# vswr.net
KiCad netlist of a schematic drawn in Altium Designer
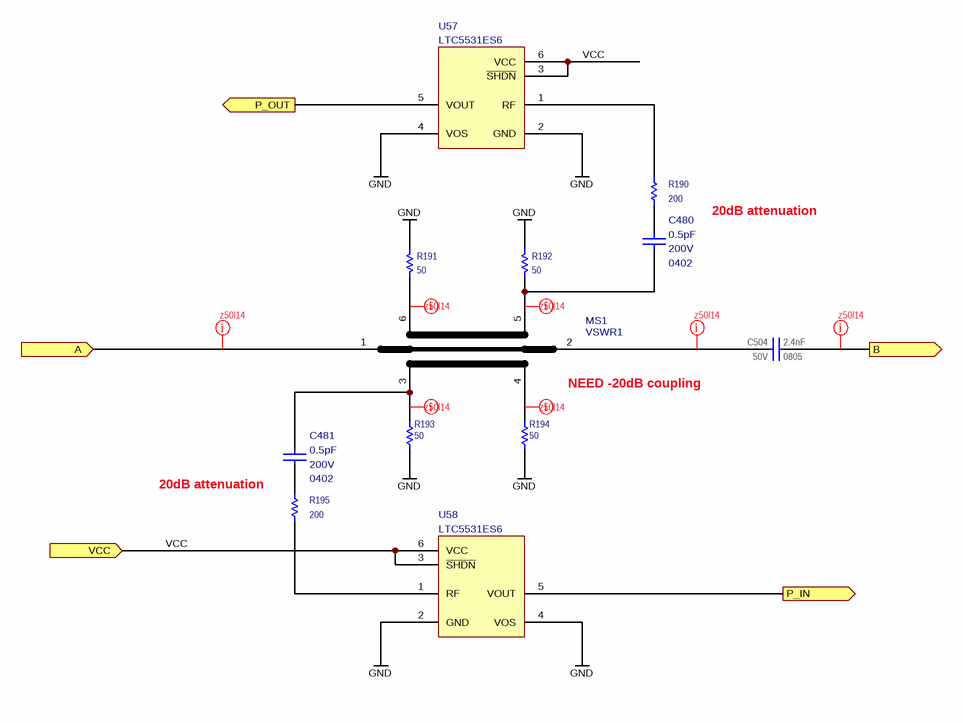
[diagram p0: vswr.SchDoc]

(export (version "E")
  (design (tool "Eeschema 10.0.6"))
  (components
    (comp (ref "C480")
      (value "0.5pF")
      (footprint "CAPC100X50X55L25N")
      (description "Ceramic Capacitor 0.5pF ±0.05pF 200V C0G 0402")
      (fields
        (field (name "MANUFACTURER") "American Technical Ceramics")
        (field (name "TOLERANCE") "±0.05pF")
        (field (name "PACKAGE") "0402")
        (field (name "VOLTAGE") "200V")
      )
      (libsource (lib "capacitors") (part "CAP"))
    )
    (comp (ref "C481")
      (value "0.5pF")
      (footprint "CAPC100X50X55L25N")
      (description "Ceramic Capacitor 0.5pF ±0.05pF 200V C0G 0402")
      (fields
        (field (name "MANUFACTURER") "American Technical Ceramics")
        (field (name "TOLERANCE") "±0.05pF")
        (field (name "PACKAGE") "0402")
        (field (name "VOLTAGE") "200V")
      )
      (libsource (lib "capacitors") (part "CAP"))
    )
    (comp (ref "C504")
      (value "2.4nF")
      (footprint "CAPC2012X145N")
      (description "Ceramic Capacitor 2.4nF 50V 0805")
      (fields
        (field (name "MANUFACTURER") "Dielectric Laboratories")
        (field (name "VOLTAGE") "50V")
        (field (name "PACKAGE") "0805")
        (field (name "Comment") "C08BL242X-5UN-X0T")
      )
      (libsource (lib "generic") (part "CAP"))
    )
    (comp (ref "MS1")
      (value "VSWR1")
      (footprint "graviton:VSWR1")
      (description "VSWR Meter Stripline")
      (libsource (lib "Graviton") (part "VSWR1"))
    )
    (comp (ref "R190")
      (value "200")
      (footprint "generic:RESC1005X40N")
      (description "Thin Film RF Resistor 200 Ohm ±0.1% 0402")
      (fields (field (name "MANUFACTURER") "Vishay") (field (name "TOLERANCE") "±0.1%"))
      (libsource (lib "Graviton") (part "RES 0603"))
    )
    (comp (ref "R191")
      (value "50")
      (footprint "generic:RESC1005X40N")
      (description "Thin Film RF Resistor 50 Ohm ±0.1% 0402")
      (fields (field (name "MANUFACTURER") "Vishay") (field (name "TOLERANCE") "±0.1%"))
      (libsource (lib "Graviton") (part "RES 0603"))
    )
    (comp (ref "R192")
      (value "50")
      (footprint "generic:RESC1005X40N")
      (description "Thin Film RF Resistor 50 Ohm ±0.1% 0402")
      (fields (field (name "MANUFACTURER") "Vishay") (field (name "TOLERANCE") "±0.1%"))
      (libsource (lib "Graviton") (part "RES 0603"))
    )
    (comp (ref "R193")
      (value "50")
      (footprint "generic:RESC1005X40N")
      (description "Thin Film RF Resistor 50 Ohm ±0.1% 0402")
      (fields (field (name "MANUFACTURER") "Vishay") (field (name "TOLERANCE") "±0.1%"))
      (libsource (lib "Graviton") (part "RES 0603"))
    )
    (comp (ref "R194")
      (value "50")
      (footprint "generic:RESC1005X40N")
      (description "Thin Film RF Resistor 50 Ohm ±0.1% 0402")
      (fields (field (name "MANUFACTURER") "Vishay") (field (name "TOLERANCE") "±0.1%"))
      (libsource (lib "Graviton") (part "RES 0603"))
    )
    (comp (ref "R195")
      (value "200")
      (footprint "generic:RESC1005X40N")
      (description "Thin Film RF Resistor 200 Ohm ±0.1% 0402")
      (fields (field (name "MANUFACTURER") "Vishay") (field (name "TOLERANCE") "±0.1%"))
      (libsource (lib "Graviton") (part "RES 0603"))
    )
    (comp (ref "U57")
      (value "LTC5531ES6")
      (footprint "generic:SOT23-6")
      (description "RF Detector")
      (fields (field (name "MANUFACTURER") "Linear Technology"))
      (libsource (lib "") (part "LTC5531ES6_1"))
    )
    (comp (ref "U58")
      (value "LTC5531ES6")
      (footprint "generic:SOT23-6")
      (description "RF Detector")
      (fields (field (name "MANUFACTURER") "Linear Technology"))
      (libsource (lib "linear") (part "LTC5531ES6"))
    )
  )
  (nets
    (net (code "1") (name "/A") (class "Default")
      (node (ref "MS1") (pin "1") (pinfunction "S1_1") (pintype "passive"))
    )
    (net (code "2") (name "/B") (class "Default")
      (node (ref "C504") (pin "1") (pinfunction "1_1") (pintype "passive"))
    )
    (net (code "3") (name "/P_IN") (class "Default")
      (node (ref "U58") (pin "5") (pinfunction "VOUT_5") (pintype "passive"))
    )
    (net (code "4") (name "/P_OUT") (class "Default")
      (node (ref "U57") (pin "5") (pinfunction "VOUT_5") (pintype "passive"))
    )
    (net (code "5") (name "/VCC") (class "Default")
      (node (ref "U57") (pin "3") (pinfunction "SHDN_3") (pintype "passive"))
      (node (ref "U57") (pin "6") (pinfunction "VCC_6") (pintype "passive"))
      (node (ref "U58") (pin "3") (pinfunction "SHDN_3") (pintype "passive"))
      (node (ref "U58") (pin "6") (pinfunction "VCC_6") (pintype "passive"))
    )
    (net (code "6") (name "GND") (class "Default")
      (node (ref "R191") (pin "1") (pinfunction "1_1") (pintype "passive"))
      (node (ref "R192") (pin "1") (pinfunction "1_1") (pintype "passive"))
      (node (ref "R193") (pin "1") (pinfunction "1_1") (pintype "passive"))
      (node (ref "R194") (pin "1") (pinfunction "1_1") (pintype "passive"))
      (node (ref "U57") (pin "2") (pinfunction "GND_2") (pintype "passive"))
      (node (ref "U57") (pin "4") (pinfunction "VOS_4") (pintype "passive"))
      (node (ref "U58") (pin "2") (pinfunction "GND_2") (pintype "passive"))
      (node (ref "U58") (pin "4") (pinfunction "VOS_4") (pintype "passive"))
    )
    (net (code "7") (name "Net-(C480-Pad1)") (class "Default")
      (node (ref "C480") (pin "1") (pinfunction "1_1") (pintype "passive"))
      (node (ref "R190") (pin "1") (pinfunction "1_1") (pintype "passive"))
    )
    (net (code "8") (name "Net-(C481-Pad2)") (class "Default")
      (node (ref "C481") (pin "2") (pinfunction "2_2") (pintype "passive"))
      (node (ref "R195") (pin "2") (pinfunction "2_2") (pintype "passive"))
    )
    (net (code "9") (name "Net-(MS1-S2)") (class "Default")
      (node (ref "C504") (pin "2") (pinfunction "2_2") (pintype "passive"))
      (node (ref "MS1") (pin "2") (pinfunction "S2_2") (pintype "passive"))
    )
    (net (code "10") (name "Net-(MS1-S3)") (class "Default")
      (node (ref "C481") (pin "1") (pinfunction "1_1") (pintype "passive"))
      (node (ref "MS1") (pin "3") (pinfunction "S3_3") (pintype "passive"))
      (node (ref "R193") (pin "2") (pinfunction "2_2") (pintype "passive"))
    )
    (net (code "11") (name "Net-(MS1-S4)") (class "Default")
      (node (ref "MS1") (pin "4") (pinfunction "S4_4") (pintype "passive"))
      (node (ref "R194") (pin "2") (pinfunction "2_2") (pintype "passive"))
    )
    (net (code "12") (name "Net-(MS1-S5)") (class "Default")
      (node (ref "C480") (pin "2") (pinfunction "2_2") (pintype "passive"))
      (node (ref "MS1") (pin "5") (pinfunction "S5_5") (pintype "passive"))
      (node (ref "R192") (pin "2") (pinfunction "2_2") (pintype "passive"))
    )
    (net (code "13") (name "Net-(MS1-S6)") (class "Default")
      (node (ref "MS1") (pin "6") (pinfunction "S6_6") (pintype "passive"))
      (node (ref "R191") (pin "2") (pinfunction "2_2") (pintype "passive"))
    )
    (net (code "14") (name "Net-(U57-RF)") (class "Default")
      (node (ref "R190") (pin "2") (pinfunction "2_2") (pintype "passive"))
      (node (ref "U57") (pin "1") (pinfunction "RF_1") (pintype "passive"))
    )
    (net (code "15") (name "Net-(U58-RF)") (class "Default")
      (node (ref "R195") (pin "1") (pinfunction "1_1") (pintype "passive"))
      (node (ref "U58") (pin "1") (pinfunction "RF_1") (pintype "passive"))
    )
  )
)
